# chicker.net
KiCad netlist of a schematic drawn in Altium Designer
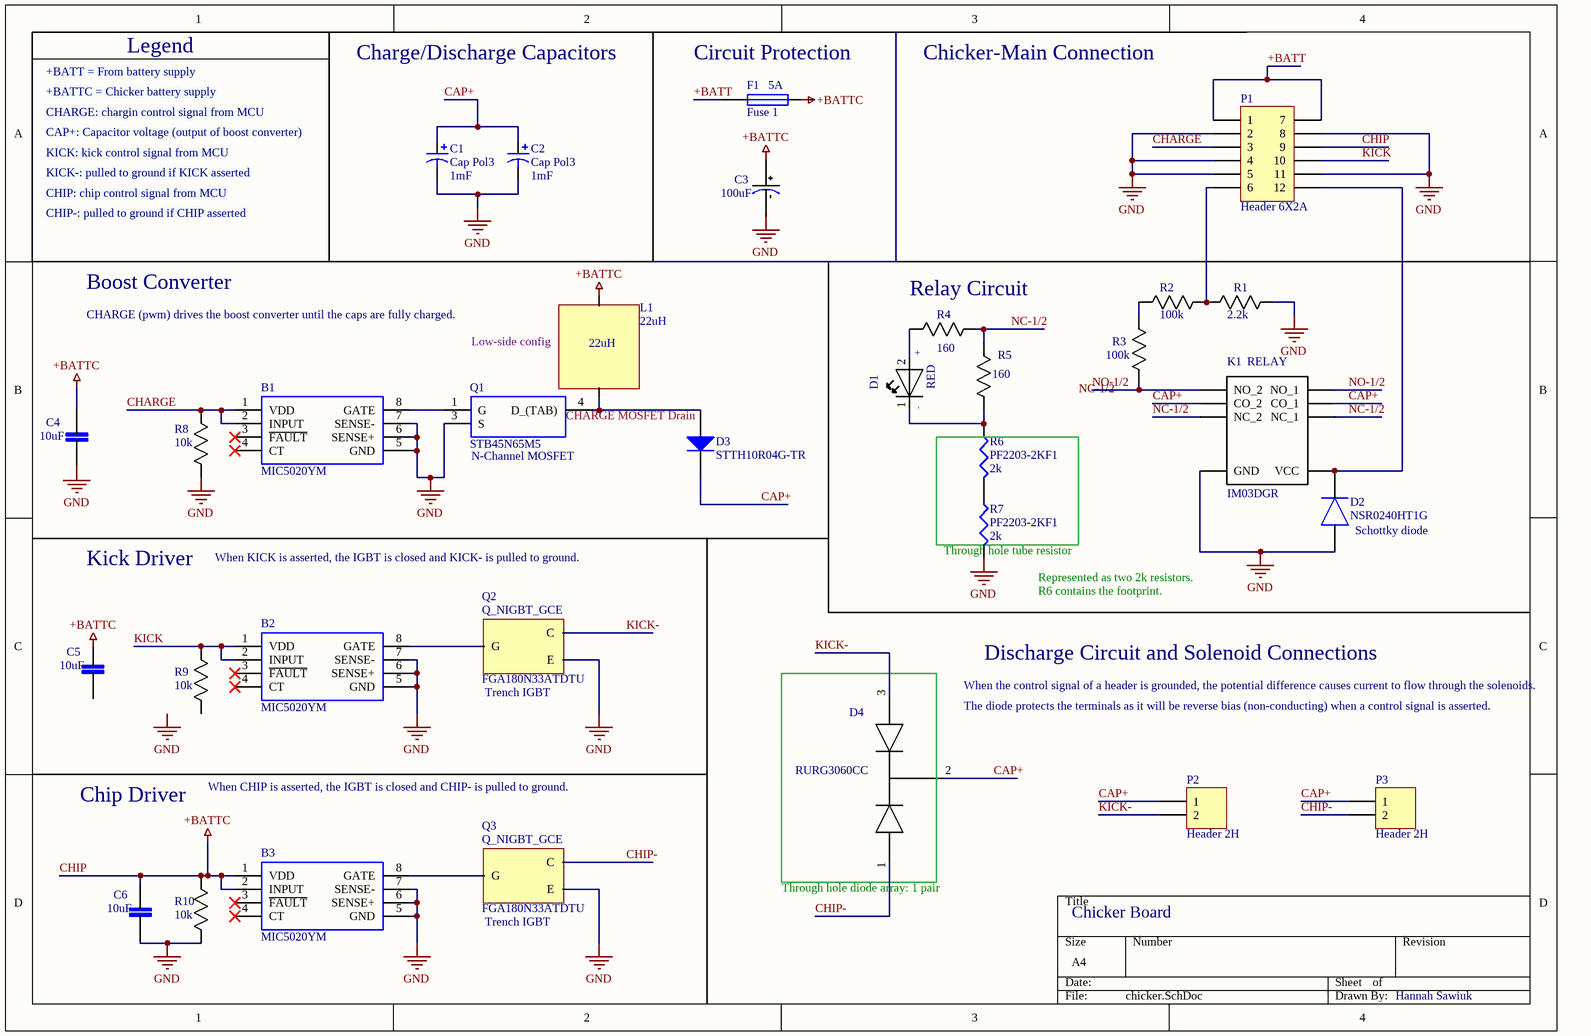
[diagram p0: chicker.SchDoc]

(export (version "E")
  (design (tool "Eeschema 10.0.6"))
  (components
    (comp (ref "B1")
      (value "MIC5020YM")
      (footprint "SOIC127P600X188-8N")
      (description "Low-Side Gate Driver IC Non-Inverting 8-SOIC")
      (fields (field (name "MP") "Microchip") (field (name "DIGI-KEY_PART_NUM") "576-1818-5-ND"))
      (libsource (lib "MIC5020YM") (part "MIC5020YM"))
    )
    (comp (ref "B2")
      (value "MIC5020YM")
      (footprint "SOIC127P600X188-8N")
      (description "Low-Side Gate Driver IC Non-Inverting 8-SOIC")
      (fields (field (name "MP") "Microchip") (field (name "DIGI-KEY_PART_NUM") "576-1818-5-ND"))
      (libsource (lib "MIC5020YM") (part "MIC5020YM"))
    )
    (comp (ref "B3")
      (value "MIC5020YM")
      (footprint "SOIC127P600X188-8N")
      (description "Low-Side Gate Driver IC Non-Inverting 8-SOIC")
      (fields (field (name "MP") "Microchip") (field (name "DIGI-KEY_PART_NUM") "576-1818-5-ND"))
      (libsource (lib "MIC5020YM") (part "MIC5020YM"))
    )
    (comp (ref "C1")
      (value "Cap Pol3")
      (footprint "C0805")
      (description "Polarized Capacitor (Surface Mount)")
      (fields
        (field (name "ALTIUM_VALUE") "1mF")
        (field (name "DIGI-KEY_PART_NUM") "565-2754-ND")
        (field (name "MF") "United Chemi-Con")
      )
      (libsource (lib "Miscellaneous Devices") (part "Cap Pol3"))
    )
    (comp (ref "C2")
      (value "Cap Pol3")
      (footprint "C0805")
      (description "Polarized Capacitor (Surface Mount)")
      (fields
        (field (name "ALTIUM_VALUE") "1mF")
        (field (name "DIGI-KEY_PART_NUM") "565-2754-ND")
        (field (name "MF") "United Chemi-Con")
      )
      (libsource (lib "Miscellaneous Devices") (part "Cap Pol3"))
    )
    (comp (ref "C3")
      (value "100uF")
      (footprint "CAPPRD350W60D800H1150B_ECA-1HM101(Primary)")
      (description "CAP ALUM 100UF 20% 50V RADIAL")
      (fields (field (name "MF") "Panasonic") (field (name "MP") "ECA-1HM101"))
      (libsource (lib "ECA-1HM101") (part "ECA-1HM101"))
    )
    (comp (ref "C4")
      (value "10uF")
      (footprint "CAPC3216X100N")
      (description "CAP CER 10UF 25V X5R 1206")
      (fields (field (name "MF") "Samsung") (field (name "MP") "CL31A106KAHNNNE"))
      (libsource (lib "") (part "CL31A226KOCLFNC_1"))
    )
    (comp (ref "C5")
      (value "10uF")
      (footprint "CAPC3216X100N")
      (description "CAP CER 10UF 25V X5R 1206")
      (fields (field (name "MF") "Samsung") (field (name "MP") "CL31A106KAHNNNE"))
      (libsource (lib "CL31A226KOCLFNC") (part "CL31A226KOCLFNC"))
    )
    (comp (ref "C6")
      (value "10uF")
      (footprint "CAPC3216X100N")
      (description "CAP CER 10UF 25V X5R 1206")
      (fields (field (name "MF") "Samsung") (field (name "MP") "CL31A106KAHNNNE"))
      (libsource (lib "CL31A226KOCLFNC") (part "CL31A226KOCLFNC"))
    )
    (comp (ref "D1")
      (value "RED")
      (footprint "WL-SMRW-1206-RECT")
      (description "LED RED CLEAR 1206 SMD")
      (fields (field (name "MF") "Lite-On Inc.") (field (name "MP") "LTST-C150CKT"))
      (libsource (lib "WL-SMRW") (part "WL-SMRW"))
    )
    (comp (ref "D2")
      (value "NSR0240HT1G")
      (footprint "SOD2512X110N")
      (description "SMT Schottky Diode, 40V dc 250mA, 3ns, 2-pin SOD-323")
      (fields (field (name "MF") "ON Semiconductor") (field (name "RS PART NUMBER") "7931024P"))
      (libsource (lib "NSR0240HT1G") (part "NSR0240HT1G"))
    )
    (comp (ref "D3")
      (value "STTH10R04G-TR")
      (footprint "DPAK508P1542X460-3N")
      (description "DIODE GEN PURP 400V 10A D2PAK")
      (fields (field (name "DIGI-KEY_PART_NUM") "497-7575-1-ND") (field (name "MF") "STMicroelectronics"))
      (libsource (lib "Miscellaneous Devices") (part "Diode 1N914"))
    )
    (comp (ref "D4")
      (value "RURG3060CC")
      (footprint "SOT93_TIP147(Primary)")
      (description "DIODE ARRAY GP 600V 30A TO247")
      (fields (field (name "DIGI-KEY_PART_NUM") "RURG3060CC-ND") (field (name "MF") "On Semiconductor"))
      (libsource (lib "Schematic Components") (part "RURG3060CC"))
    )
    (comp (ref "F1")
      (value "Fuse 1")
      (footprint "FUSM3216X140N")
      (description "FUSE BOARD MOUNT 5A 32VDC 1206")
      (fields (field (name "DIGI-KEY_PART_NUM") "F3539CT-ND") (field (name "MF") "Littelfuse Inc."))
      (libsource (lib "Miscellaneous Devices") (part "Fuse 1"))
    )
    (comp (ref "K1")
      (value "IM03DGR")
      (footprint "GULLWINGS")
      (description "Relay, Signal, Dpdt, 250vac, 220vdc, 5a")
      (fields
        (field (name "MF") "TE Connectivity")
        (field (name "ALTIUM_VALUE") "RELAY")
        (field (name "MOUSER_PART_NUM") "655-IM03DGR")
      )
      (libsource (lib "IM03DGR") (part "IM03DGR"))
    )
    (comp (ref "L1")
      (value "22uH")
      (footprint "PCBComponent_1")
      (libsource (lib "Schematic Components") (part "Inductor 22uH"))
    )
    (comp (ref "P1")
      (value "Header 6X2A")
      (footprint "HDR2X6_CEN")
      (description "Header, 6-Pin, Dual row")
      (fields
        (field (name "DIGI-KEY_PART_NUM") "S7074-ND")
        (field (name "MF") "Sullins Connector Solutions")
        (field (name "PUBLISHER") "Altium Limited")
      )
      (libsource (lib "Miscellaneous Connectors") (part "Header 6X2A"))
    )
    (comp (ref "P2")
      (value "Header 2H")
      (footprint "HDR1X2H")
      (description "2 Positions Header Connector 0.100\" (2.54mm) Through Hole, Right Angle Tin")
      (fields (field (name "DIGI-KEY_PART_NUM") "WM4300-ND") (field (name "MF") "Molex, LLC"))
      (libsource (lib "Miscellaneous Connectors") (part "Header 2H"))
    )
    (comp (ref "P3")
      (value "Header 2H")
      (footprint "HDR1X2H")
      (description "2 Positions Header Connector 0.100\" (2.54mm) Through Hole, Right Angle Tin")
      (fields (field (name "DIGI-KEY_PART_NUM") "WM4300-ND") (field (name "MF") "Molex, LLC"))
      (libsource (lib "Miscellaneous Connectors") (part "Header 2H"))
    )
    (comp (ref "Q1")
      (value "STB45N65M5")
      (footprint "TO254P1542X460-3N")
      (description "MOSFET N CH 650V 35A D2PAK")
      (fields (field (name "MF") "STMicroelectronics") (field (name "DIGI-KEY_PART_NUM") "497-12940-1-ND"))
      (libsource (lib "STB45N65M5") (part "STB45N65M5"))
    )
    (comp (ref "Q2")
      (value "FGA180N33ATDTU")
      (footprint "TO-3PN_V_FDA69N25(Primary)")
      (description "IGBT Trench 330V 180A 390W Through Hole TO-3P")
      (fields (field (name "DIGI-KEY_PART_NUM") "FGA180N33ATDTU-ND") (field (name "MF") "ON Semiconductor"))
      (libsource (lib "Schematic Components") (part "FGA180N33ATDTU"))
    )
    (comp (ref "Q3")
      (value "FGA180N33ATDTU")
      (footprint "TO-3PN_V_FDA69N25(Primary)")
      (description "IGBT Trench 330V 180A 390W Through Hole TO-3P")
      (fields (field (name "DIGI-KEY_PART_NUM") "FGA180N33ATDTU-ND") (field (name "MF") "ON Semiconductor"))
      (libsource (lib "Schematic Components") (part "FGA180N33ATDTU"))
    )
    (comp (ref "R1")
      (value "2.2k")
      (footprint "RESC2013X65N")
      (description "RES SMD 2.2K OHM 1% 1/8W 0805")
      (fields (field (name "MP") "RC0805FR-072K2L") (field (name "MF") "Yageo"))
      (libsource (lib "RC0805FR-072K2L") (part "RC0805FR-072K2L"))
    )
    (comp (ref "R2")
      (value "100k")
      (footprint "RESC2013X65N")
      (description "RES SMD 100K OHM 1% 1/8W 0805")
      (fields (field (name "MP") "RC0805FR-07100KL") (field (name "MF") "Yageo"))
      (libsource (lib "RC0805FR-072K2L") (part "RC0805FR-072K2L"))
    )
    (comp (ref "R3")
      (value "100k")
      (footprint "RESC2013X65N")
      (description "RES SMD 100K OHM 1% 1/8W 0805")
      (fields (field (name "MP") "RC0805FR-07100KL") (field (name "MF") "Yageo"))
      (libsource (lib "RC0805FR-072K2L") (part "RC0805FR-072K2L"))
    )
    (comp (ref "R4")
      (value "160")
      (footprint "RESC2013X65N")
      (description "RES SMD 160 OHM 1% 1/8W 0805")
      (fields (field (name "MP") "RC0805FR-07160RL") (field (name "MF") "Yageo"))
      (libsource (lib "RC0805FR-072K2L") (part "RC0805FR-072K2L"))
    )
    (comp (ref "R5")
      (value "160")
      (footprint "RESC2013X65N")
      (description "RES SMD 160 OHM 1% 1/8W 0805")
      (fields (field (name "MP") "RC0805FR-07160RL") (field (name "MF") "Yageo"))
      (libsource (lib "RC0805FR-072K2L") (part "RC0805FR-072K2L"))
    )
    (comp (ref "R6")
      (value "PF2203-2KF1")
      (footprint "POWER_DIODE")
      (description "RES 2K OHM 35W 1% TO220")
      (fields
        (field (name "ALTIUM_VALUE") "2k")
        (field (name "DIGI-KEY_PART_NUM") "696-1170-ND")
        (field (name "MF") "Riedon")
        (field (name "PUBLISHER") "Altium Limited")
      )
      (libsource (lib "Miscellaneous Devices") (part "Res3"))
    )
    (comp (ref "R7")
      (value "PF2203-2KF1")
      (footprint "POWER_DIODE")
      (description "RES 2K OHM 35W 1% TO220")
      (fields
        (field (name "ALTIUM_VALUE") "2k")
        (field (name "DIGI-KEY_PART_NUM") "696-1170-ND")
        (field (name "MF") "Riedon")
        (field (name "PUBLISHER") "Altium Limited")
      )
      (libsource (lib "Miscellaneous Devices") (part "Res3"))
    )
    (comp (ref "R8")
      (value "10k")
      (footprint "RESC2013X65N")
      (description "RES SMD 10K OHM 1% 1/8W 0805")
      (fields (field (name "MP") "RC0805FR-0710KL") (field (name "MF") "Yageo"))
      (libsource (lib "RC0805FR-072K2L") (part "RC0805FR-072K2L"))
    )
    (comp (ref "R9")
      (value "10k")
      (footprint "RESC2013X65N")
      (description "RES SMD 10K OHM 1% 1/8W 0805")
      (fields (field (name "MP") "RC0805FR-0710KL") (field (name "MF") "Yageo"))
      (libsource (lib "RC0805FR-072K2L") (part "RC0805FR-072K2L"))
    )
    (comp (ref "R10")
      (value "10k")
      (footprint "RESC2013X65N")
      (description "RES SMD 10K OHM 1% 1/8W 0805")
      (fields (field (name "MP") "RC0805FR-0710KL") (field (name "MF") "Yageo"))
      (libsource (lib "RC0805FR-072K2L") (part "RC0805FR-072K2L"))
    )
  )
  (nets
    (net (code "1") (name "+BATTC") (class "Default")
      (node (ref "B3") (pin "1") (pinfunction "VDD_1") (pintype "power_in"))
      (node (ref "B3") (pin "2") (pinfunction "INPUT_2") (pintype "passive"))
      (node (ref "C3") (pin "POS") (pinfunction "POS_POS") (pintype "passive"))
      (node (ref "C4") (pin "1") (pinfunction "1_1") (pintype "passive"))
      (node (ref "C6") (pin "1") (pinfunction "1_1") (pintype "passive"))
      (node (ref "L1") (pin "1") (pinfunction "1_1") (pintype "passive"))
      (node (ref "P1") (pin "9") (pinfunction "9_9") (pintype "passive"))
      (node (ref "R10") (pin "1") (pinfunction "R1_1") (pintype "passive"))
    )
    (net (code "2") (name "/+BATT") (class "Default")
      (node (ref "F1") (pin "2") (pinfunction "2_2") (pintype "passive"))
      (node (ref "P1") (pin "1") (pinfunction "1_1") (pintype "passive"))
      (node (ref "P1") (pin "7") (pinfunction "7_7") (pintype "passive"))
    )
    (net (code "3") (name "/CAP+") (class "Default")
      (node (ref "C1") (pin "1") (pinfunction "1_1") (pintype "passive"))
      (node (ref "C2") (pin "1") (pinfunction "1_1") (pintype "passive"))
      (node (ref "D3") (pin "2") (pinfunction "K_2") (pintype "passive"))
      (node (ref "D4") (pin "2") (pinfunction "6_2") (pintype "passive"))
      (node (ref "K1") (pin "3") (pinfunction "CO_1_3") (pintype "passive"))
      (node (ref "K1") (pin "6") (pinfunction "CO_2_6") (pintype "passive"))
      (node (ref "P2") (pin "1") (pinfunction "1_1") (pintype "passive"))
      (node (ref "P3") (pin "1") (pinfunction "1_1") (pintype "passive"))
    )
    (net (code "4") (name "/CHARGE") (class "Default")
      (node (ref "B1") (pin "1") (pinfunction "VDD_1") (pintype "power_in"))
      (node (ref "B1") (pin "2") (pinfunction "INPUT_2") (pintype "passive"))
      (node (ref "P1") (pin "3") (pinfunction "3_3") (pintype "passive"))
      (node (ref "R8") (pin "1") (pinfunction "R1_1") (pintype "passive"))
    )
    (net (code "5") (name "/CHIP-") (class "Default")
      (node (ref "D4") (pin "1") (pinfunction "7_1") (pintype "passive"))
      (node (ref "P3") (pin "2") (pinfunction "2_2") (pintype "passive"))
      (node (ref "Q3") (pin "4") (pinfunction "C_4") (pintype "passive"))
    )
    (net (code "6") (name "/KICK") (class "Default")
      (node (ref "B2") (pin "1") (pinfunction "VDD_1") (pintype "power_in"))
      (node (ref "B2") (pin "2") (pinfunction "INPUT_2") (pintype "passive"))
      (node (ref "P1") (pin "10") (pinfunction "10_10") (pintype "passive"))
      (node (ref "R9") (pin "1") (pinfunction "R1_1") (pintype "passive"))
    )
    (net (code "7") (name "/KICK-") (class "Default")
      (node (ref "D4") (pin "3") (pinfunction "1_3") (pintype "passive"))
      (node (ref "P2") (pin "2") (pinfunction "2_2") (pintype "passive"))
      (node (ref "Q2") (pin "4") (pinfunction "C_4") (pintype "passive"))
    )
    (net (code "8") (name "/NC-1{slash}2") (class "Default")
      (node (ref "K1") (pin "2") (pinfunction "NC_1_2") (pintype "passive"))
      (node (ref "K1") (pin "7") (pinfunction "NC_2_7") (pintype "passive"))
      (node (ref "R4") (pin "1") (pinfunction "R1_1") (pintype "passive"))
      (node (ref "R5") (pin "2") (pinfunction "R2_2") (pintype "passive"))
    )
    (net (code "9") (name "/NO-1{slash}2") (class "Default")
      (node (ref "K1") (pin "4") (pinfunction "NO_1_4") (pintype "passive"))
      (node (ref "K1") (pin "5") (pinfunction "NO_2_5") (pintype "passive"))
      (node (ref "R3") (pin "1") (pinfunction "R1_1") (pintype "passive"))
    )
    (net (code "10") (name "GND") (class "Default")
      (node (ref "B1") (pin "5") (pinfunction "GND_5") (pintype "passive"))
      (node (ref "B1") (pin "6") (pinfunction "SENSE+_6") (pintype "passive"))
      (node (ref "B1") (pin "7") (pinfunction "SENSE-_7") (pintype "passive"))
      (node (ref "B2") (pin "5") (pinfunction "GND_5") (pintype "passive"))
      (node (ref "B2") (pin "6") (pinfunction "SENSE+_6") (pintype "passive"))
      (node (ref "B2") (pin "7") (pinfunction "SENSE-_7") (pintype "passive"))
      (node (ref "B3") (pin "5") (pinfunction "GND_5") (pintype "passive"))
      (node (ref "B3") (pin "6") (pinfunction "SENSE+_6") (pintype "passive"))
      (node (ref "B3") (pin "7") (pinfunction "SENSE-_7") (pintype "passive"))
      (node (ref "C1") (pin "2") (pinfunction "2_2") (pintype "passive"))
      (node (ref "C2") (pin "2") (pinfunction "2_2") (pintype "passive"))
      (node (ref "C3") (pin "NEG") (pinfunction "NEG_NEG") (pintype "passive"))
      (node (ref "C4") (pin "2") (pinfunction "2_2") (pintype "passive"))
      (node (ref "C6") (pin "2") (pinfunction "2_2") (pintype "passive"))
      (node (ref "D2") (pin "2") (pinfunction "A_2") (pintype "passive"))
      (node (ref "K1") (pin "8") (pinfunction "GND_8") (pintype "power_in"))
      (node (ref "P1") (pin "11") (pinfunction "11_11") (pintype "passive"))
      (node (ref "P1") (pin "2") (pinfunction "2_2") (pintype "passive"))
      (node (ref "P1") (pin "4") (pinfunction "4_4") (pintype "passive"))
      (node (ref "P1") (pin "5") (pinfunction "5_5") (pintype "passive"))
      (node (ref "P1") (pin "8") (pinfunction "8_8") (pintype "passive"))
      (node (ref "Q1") (pin "3") (pinfunction "S_3") (pintype "passive"))
      (node (ref "Q2") (pin "3") (pinfunction "E_3") (pintype "passive"))
      (node (ref "Q3") (pin "3") (pinfunction "E_3") (pintype "passive"))
      (node (ref "R1") (pin "1") (pinfunction "R1_1") (pintype "passive"))
      (node (ref "R10") (pin "2") (pinfunction "R2_2") (pintype "passive"))
      (node (ref "R7") (pin "2") (pinfunction "2_2") (pintype "passive"))
      (node (ref "R8") (pin "2") (pinfunction "R2_2") (pintype "passive"))
    )
    (net (code "11") (name "Net-(B1-GATE)") (class "Default")
      (node (ref "B1") (pin "8") (pinfunction "GATE_8") (pintype "passive"))
      (node (ref "Q1") (pin "1") (pinfunction "G_1") (pintype "passive"))
    )
    (net (code "12") (name "Net-(B2-GATE)") (class "Default")
      (node (ref "B2") (pin "8") (pinfunction "GATE_8") (pintype "passive"))
      (node (ref "Q2") (pin "G") (pinfunction "G_G") (pintype "passive"))
    )
    (net (code "13") (name "Net-(B3-GATE)") (class "Default")
      (node (ref "B3") (pin "8") (pinfunction "GATE_8") (pintype "passive"))
      (node (ref "Q3") (pin "G") (pinfunction "G_G") (pintype "passive"))
    )
    (net (code "14") (name "Net-(D1-NEG)") (class "Default")
      (node (ref "D1") (pin "1") (pinfunction "NEG_1") (pintype "bidirectional"))
      (node (ref "R5") (pin "1") (pinfunction "R1_1") (pintype "passive"))
      (node (ref "R6") (pin "1") (pinfunction "1_1") (pintype "passive"))
    )
    (net (code "15") (name "Net-(D1-POS)") (class "Default")
      (node (ref "D1") (pin "2") (pinfunction "POS_2") (pintype "bidirectional"))
      (node (ref "R4") (pin "2") (pinfunction "R2_2") (pintype "passive"))
    )
    (net (code "16") (name "Net-(D2-K)") (class "Default")
      (node (ref "D2") (pin "1") (pinfunction "K_1") (pintype "passive"))
      (node (ref "K1") (pin "1") (pinfunction "VCC_1") (pintype "power_in"))
      (node (ref "P1") (pin "12") (pinfunction "12_12") (pintype "passive"))
    )
    (net (code "17") (name "Net-(D3-A)") (class "Default")
      (node (ref "D3") (pin "1") (pinfunction "A_1") (pintype "passive"))
      (node (ref "L1") (pin "0") (pinfunction "0_0") (pintype "passive"))
      (node (ref "Q1") (pin "4") (pinfunction "D_(TAB)_4") (pintype "passive"))
    )
    (net (code "18") (name "Net-(R1-R2)") (class "Default")
      (node (ref "P1") (pin "6") (pinfunction "6_6") (pintype "passive"))
      (node (ref "R1") (pin "2") (pinfunction "R2_2") (pintype "passive"))
      (node (ref "R2") (pin "2") (pinfunction "R2_2") (pintype "passive"))
    )
    (net (code "19") (name "Net-(R2-R1)") (class "Default")
      (node (ref "R2") (pin "1") (pinfunction "R1_1") (pintype "passive"))
      (node (ref "R3") (pin "2") (pinfunction "R2_2") (pintype "passive"))
    )
    (net (code "20") (name "Net-(R6-Pad2)") (class "Default")
      (node (ref "R6") (pin "2") (pinfunction "2_2") (pintype "passive"))
      (node (ref "R7") (pin "1") (pinfunction "1_1") (pintype "passive"))
    )
    (net (code "21") (name "unconnected-(B1-CT-Pad4)") (class "Default")
      (node (ref "B1") (pin "4") (pinfunction "CT_4") (pintype "passive+no_connect"))
    )
    (net (code "22") (name "unconnected-(B1-FAULT-Pad3)") (class "Default")
      (node (ref "B1") (pin "3") (pinfunction "FAULT_3") (pintype "passive+no_connect"))
    )
    (net (code "23") (name "unconnected-(B2-CT-Pad4)") (class "Default")
      (node (ref "B2") (pin "4") (pinfunction "CT_4") (pintype "passive+no_connect"))
    )
    (net (code "24") (name "unconnected-(B2-FAULT-Pad3)") (class "Default")
      (node (ref "B2") (pin "3") (pinfunction "FAULT_3") (pintype "passive+no_connect"))
    )
    (net (code "25") (name "unconnected-(B3-CT-Pad4)") (class "Default")
      (node (ref "B3") (pin "4") (pinfunction "CT_4") (pintype "passive+no_connect"))
    )
    (net (code "26") (name "unconnected-(B3-FAULT-Pad3)") (class "Default")
      (node (ref "B3") (pin "3") (pinfunction "FAULT_3") (pintype "passive+no_connect"))
    )
    (net (code "27") (name "unconnected-(C5-Pad1)") (class "Default")
      (node (ref "C5") (pin "1") (pinfunction "1_1") (pintype "passive"))
    )
    (net (code "28") (name "unconnected-(C5-Pad2)") (class "Default")
      (node (ref "C5") (pin "2") (pinfunction "2_2") (pintype "passive"))
    )
    (net (code "29") (name "unconnected-(F1-Pad1)") (class "Default")
      (node (ref "F1") (pin "1") (pinfunction "1_1") (pintype "passive"))
    )
    (net (code "30") (name "unconnected-(R9-R2-Pad2)") (class "Default")
      (node (ref "R9") (pin "2") (pinfunction "R2_2") (pintype "passive"))
    )
  )
)
